# 411618_029_3_3.net
KiCad netlist of a schematic drawn in Altium Designer
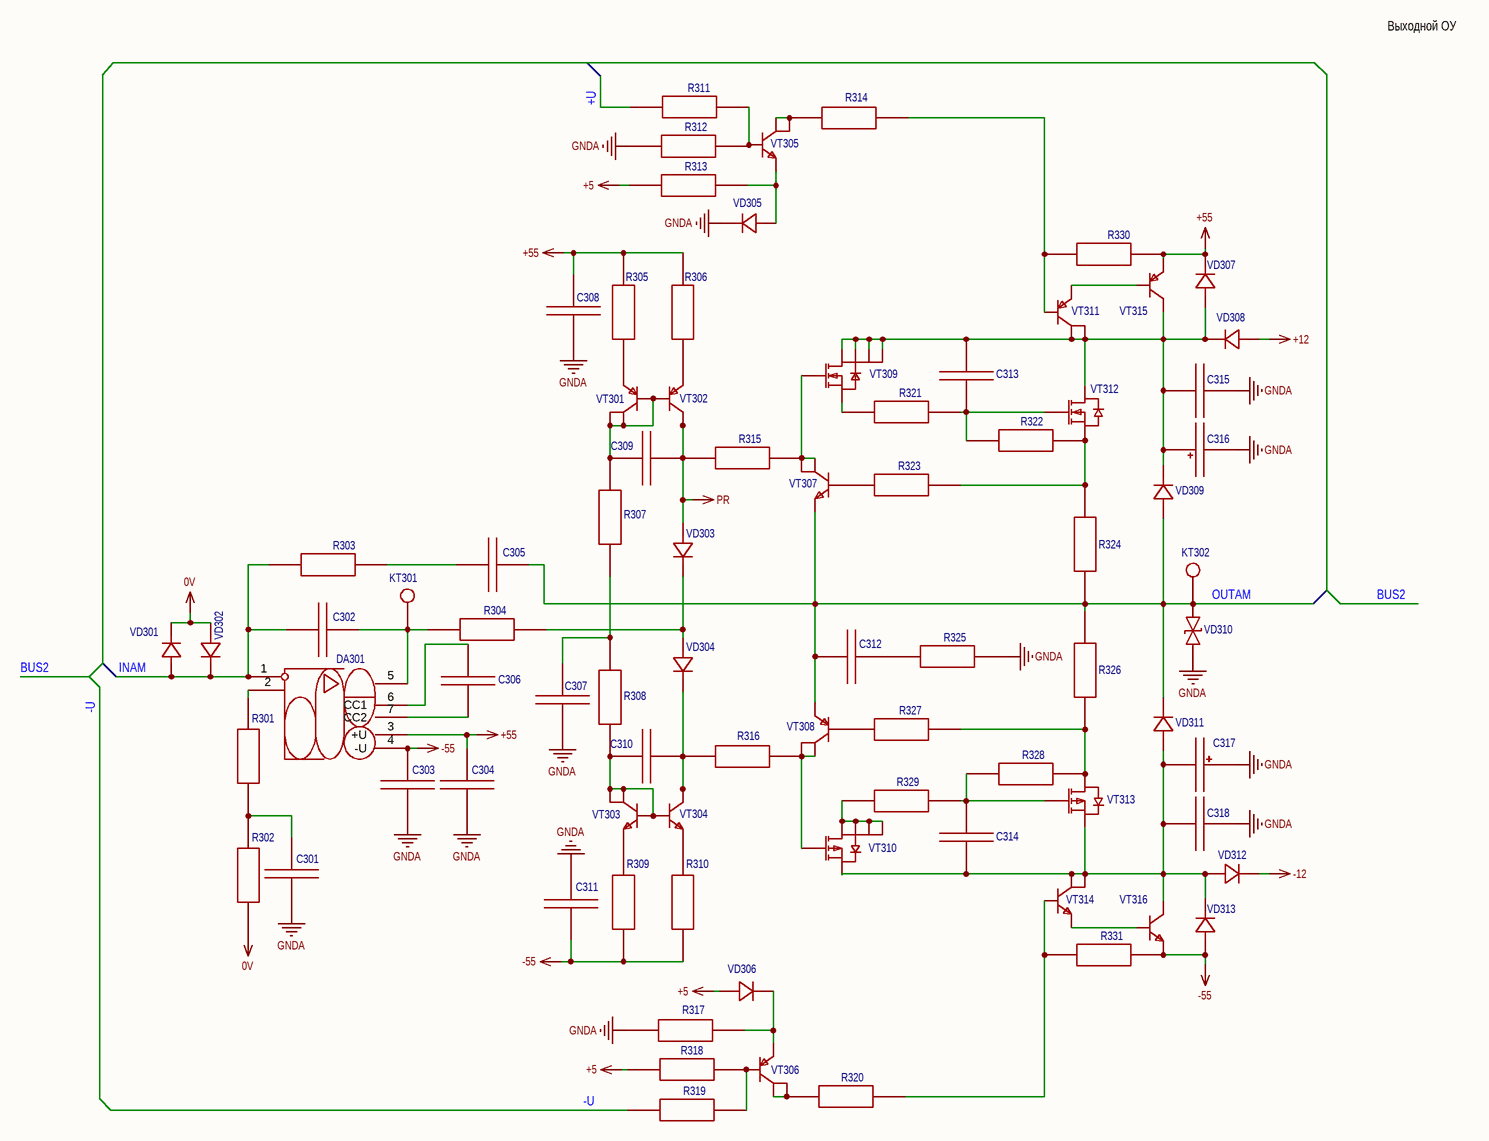
[diagram p0: УШЯИ.411618.029Э Э3 Лист 3.schdoc]

(export (version "E")
  (design (tool "Eeschema 10.0.6"))
  (components
    (comp (ref "C301")
      (value "Конденсатор SMD 1мкФ 100В X7R 10% [0805]")
      (footprint "C0805")
      (fields (field (name "MANUFACTURER PART") "C0805") (field (name "CONTRIBUTOR") "jordanjin"))
      (libsource (lib "altium-import") (part "root_1_Конденсатор SMD 1мкФ 100В X7R 10% [0805]_"))
    )
    (comp (ref "C302")
      (value "Конденсатор SMD 33пФ 100В X7R 10% [0805]")
      (footprint "C0805")
      (fields (field (name "MANUFACTURER PART") "C0805") (field (name "CONTRIBUTOR") "jordanjin"))
      (libsource (lib "altium-import") (part "root_2_Конденсатор SMD 33пФ 100В X7R 10% [0805]_"))
    )
    (comp (ref "C303")
      (value "Конденсатор SMD 68нФ 100В X7R 10% [0805]")
      (footprint "C0805")
      (fields (field (name "MANUFACTURER PART") "C0805") (field (name "CONTRIBUTOR") "jordanjin"))
      (libsource (lib "altium-import") (part "root_1_Конденсатор SMD 68нФ 100В X7R 10% [0805]_"))
    )
    (comp (ref "C304")
      (value "Конденсатор SMD 68нФ 100В X7R 10% [0805]")
      (footprint "C0805")
      (fields (field (name "MANUFACTURER PART") "C0805") (field (name "CONTRIBUTOR") "jordanjin"))
      (libsource (lib "altium-import") (part "root_1_Конденсатор SMD 68нФ 100В X7R 10% [0805]_"))
    )
    (comp (ref "C305")
      (value "Конденсатор SMD 10пФ 100В X7R 10% [0805]")
      (footprint "C0805")
      (fields (field (name "MANUFACTURER PART") "C0805") (field (name "CONTRIBUTOR") "jordanjin"))
      (libsource (lib "altium-import") (part "root_2_Конденсатор SMD 10пФ 100В X7R 10% [0805]_"))
    )
    (comp (ref "C306")
      (value "Конденсатор SMD 10пФ 100В X7R 10% [0805]")
      (footprint "C0805")
      (fields (field (name "MANUFACTURER PART") "C0805") (field (name "CONTRIBUTOR") "jordanjin"))
      (libsource (lib "altium-import") (part "root_3_Конденсатор SMD 10пФ 100В X7R 10% [0805]_"))
    )
    (comp (ref "C307")
      (value "Конденсатор SMD 68нФ 250В X7R 10% [0805]")
      (footprint "C0805")
      (fields (field (name "MANUFACTURER PART") "C0805") (field (name "CONTRIBUTOR") "jordanjin"))
      (libsource (lib "altium-import") (part "root_1_Конденсатор SMD 68нФ 250В X7R 10% [0805]_"))
    )
    (comp (ref "C308")
      (value "Конденсатор SMD 68нФ 250В X7R 10% [0805]")
      (footprint "C0805")
      (fields (field (name "MANUFACTURER PART") "C0805") (field (name "CONTRIBUTOR") "jordanjin"))
      (libsource (lib "altium-import") (part "root_3_Конденсатор SMD 68нФ 250В X7R 10% [0805]_"))
    )
    (comp (ref "C309")
      (value "Конденсатор SMD 10пФ 100В X7R 10% [0805]")
      (footprint "C0805")
      (fields (field (name "MANUFACTURER PART") "C0805") (field (name "CONTRIBUTOR") "jordanjin"))
      (libsource (lib "altium-import") (part "root_2_Конденсатор SMD 10пФ 100В X7R 10% [0805]_"))
    )
    (comp (ref "C310")
      (value "Конденсатор SMD 10пФ 100В X7R 10% [0805]")
      (footprint "C0805")
      (fields (field (name "MANUFACTURER PART") "C0805") (field (name "CONTRIBUTOR") "jordanjin"))
      (libsource (lib "") (part "root_2_Конденсатор SMD 10пФ 100В X7R 10% [0805]__1"))
    )
    (comp (ref "C311")
      (value "Конденсатор SMD 68нФ 250В X7R 10% [0805]")
      (footprint "C0805")
      (fields (field (name "MANUFACTURER PART") "C0805") (field (name "CONTRIBUTOR") "jordanjin"))
      (libsource (lib "altium-import") (part "root_3_Конденсатор SMD 68нФ 250В X7R 10% [0805]_"))
    )
    (comp (ref "C312")
      (value "Конденсатор SMD 10пФ 100В X7R 10% [0805]")
      (footprint "C0805")
      (fields (field (name "MANUFACTURER PART") "C0805") (field (name "CONTRIBUTOR") "jordanjin"))
      (libsource (lib "altium-import") (part "root_0_Конденсатор SMD 10пФ 100В X7R 10% [0805]_"))
    )
    (comp (ref "C313")
      (value "Конденсатор SMD 10пФ 100В X7R 10% [0805]")
      (footprint "C0805")
      (fields (field (name "MANUFACTURER PART") "C0805") (field (name "CONTRIBUTOR") "jordanjin"))
      (libsource (lib "altium-import") (part "root_3_Конденсатор SMD 10пФ 100В X7R 10% [0805]_"))
    )
    (comp (ref "C314")
      (value "Конденсатор SMD 10пФ 100В X7R 10% [0805]")
      (footprint "C0805")
      (fields (field (name "MANUFACTURER PART") "C0805") (field (name "CONTRIBUTOR") "jordanjin"))
      (libsource (lib "altium-import") (part "root_3_Конденсатор SMD 10пФ 100В X7R 10% [0805]_"))
    )
    (comp (ref "C315")
      (value "Конденсатор SMD 10пФ 100В X7R 10% [0805]")
      (footprint "C0805")
      (fields (field (name "MANUFACTURER PART") "C0805") (field (name "CONTRIBUTOR") "jordanjin"))
      (libsource (lib "altium-import") (part "root_0_Конденсатор SMD 10пФ 100В X7R 10% [0805]_"))
    )
    (comp (ref "C316")
      (value "ECAP (К50-35), 220мкФ, 100В, 105°C, 13x25, p:5мм")
      (footprint "CAP-TH_BD13.0-P5.00-D0.6-FD")
      (fields
        (field (name "MANUFACTURER") "JB Capacitors")
        (field (name "MANUFACTURER PART") "JRB2A221M05001300250000B")
        (field (name "CONTRIBUTOR") "jordanjin")
      )
      (libsource (lib "altium-import") (part "root_1_ECAP (К50-35), 220мкФ, 100В, 105°C, 13x25, p{colon}5мм_"))
    )
    (comp (ref "C317")
      (value "ECAP (К50-35), 220мкФ, 100В, 105°C, 13x25, p:5мм")
      (footprint "CAP-TH_BD13.0-P5.00-D0.6-FD")
      (fields
        (field (name "MANUFACTURER") "JB Capacitors")
        (field (name "MANUFACTURER PART") "JRB2A221M05001300250000B")
        (field (name "CONTRIBUTOR") "jordanjin")
      )
      (libsource (lib "altium-import") (part "root_3_ECAP (К50-35), 220мкФ, 100В, 105°C, 13x25, p{colon}5мм_"))
    )
    (comp (ref "C318")
      (value "Конденсатор SMD 10пФ 100В X7R 10% [0805]")
      (footprint "C0805")
      (fields (field (name "MANUFACTURER PART") "C0805") (field (name "CONTRIBUTOR") "jordanjin"))
      (libsource (lib "altium-import") (part "root_0_Конденсатор SMD 10пФ 100В X7R 10% [0805]_"))
    )
    (comp (ref "DA301")
      (value "Операционный усилитель PA340CC [TH]")
      (fields
        (field (name "MANUFACTURER") "Apex Microtechnology")
        (field (name "MANUFACTURER PART") "PA340CC")
        (field (name "CONTRIBUTOR") "jordanjin")
      )
      (libsource (lib "altium-import") (part "root_0_Операционный усилитель PA340CC [TH]_"))
    )
    (comp (ref "KT301")
      (value "Control point")
      (fields (field (name "CONTRIBUTOR") "jordanjin"))
      (libsource (lib "altium-import") (part "root_2_Control point_"))
    )
    (comp (ref "KT302")
      (value "Control point")
      (fields (field (name "CONTRIBUTOR") "jordanjin"))
      (libsource (lib "altium-import") (part "root_2_Control point_"))
    )
    (comp (ref "R301")
      (value "Резистор 4.6кОм 0,125Вт 1% [0805]")
      (footprint "R0805")
      (fields (field (name "MANUFACTURER PART") "R0805") (field (name "CONTRIBUTOR") "jordanjin"))
      (libsource (lib "altium-import") (part "root_1_Резистор 4.6кОм 0,125Вт 1% [0805]_"))
    )
    (comp (ref "R302")
      (value "Резистор 1.2кОм 0,125Вт 1% [0805]")
      (footprint "R0805")
      (fields (field (name "MANUFACTURER PART") "R0805") (field (name "CONTRIBUTOR") "jordanjin"))
      (libsource (lib "altium-import") (part "root_1_Резистор 1.2кОм 0,125Вт 1% [0805]_"))
    )
    (comp (ref "R303")
      (value "Резистор 1.8кОм 0,125Вт 1% [0805]")
      (footprint "R0805")
      (fields (field (name "MANUFACTURER PART") "R0805") (field (name "CONTRIBUTOR") "jordanjin"))
      (libsource (lib "altium-import") (part "root_2_Резистор 1.8кОм 0,125Вт 1% [0805]_"))
    )
    (comp (ref "R304")
      (value "Резистор 1.2кОм 0,125Вт 1% [0805]")
      (footprint "R0805")
      (fields (field (name "MANUFACTURER PART") "R0805") (field (name "CONTRIBUTOR") "jordanjin"))
      (libsource (lib "altium-import") (part "root_2_Резистор 1.2кОм 0,125Вт 1% [0805]_"))
    )
    (comp (ref "R305")
      (value "Резистор 220Ом 0,125Вт 1% [0805]")
      (footprint "R0805")
      (fields (field (name "MANUFACTURER PART") "R0805") (field (name "CONTRIBUTOR") "jordanjin"))
      (libsource (lib "") (part "root_3_Резистор 220Ом 0,125Вт 1% [0805]__1"))
    )
    (comp (ref "R306")
      (value "Резистор 220Ом 0,125Вт 1% [0805]")
      (footprint "R0805")
      (fields (field (name "MANUFACTURER PART") "R0805") (field (name "CONTRIBUTOR") "jordanjin"))
      (libsource (lib "") (part "root_3_Резистор 220Ом 0,125Вт 1% [0805]__1"))
    )
    (comp (ref "R307")
      (value "Резистор 22кОм 0,125Вт 1% [0805]")
      (footprint "R0805")
      (fields (field (name "MANUFACTURER PART") "R0805") (field (name "CONTRIBUTOR") "jordanjin"))
      (libsource (lib "") (part "root_3_Резистор 22кОм 0,125Вт 1% [0805]__1"))
    )
    (comp (ref "R308")
      (value "Резистор 22кОм 0,125Вт 1% [0805]")
      (footprint "R0805")
      (fields (field (name "MANUFACTURER PART") "R0805") (field (name "CONTRIBUTOR") "jordanjin"))
      (libsource (lib "altium-import") (part "root_3_Резистор 22кОм 0,125Вт 1% [0805]_"))
    )
    (comp (ref "R309")
      (value "Резистор 220Ом 0,125Вт 1% [0805]")
      (footprint "R0805")
      (fields (field (name "MANUFACTURER PART") "R0805") (field (name "CONTRIBUTOR") "jordanjin"))
      (libsource (lib "altium-import") (part "root_3_Резистор 220Ом 0,125Вт 1% [0805]_"))
    )
    (comp (ref "R310")
      (value "Резистор 220Ом 0,125Вт 1% [0805]")
      (footprint "R0805")
      (fields (field (name "MANUFACTURER PART") "R0805") (field (name "CONTRIBUTOR") "jordanjin"))
      (libsource (lib "altium-import") (part "root_3_Резистор 220Ом 0,125Вт 1% [0805]_"))
    )
    (comp (ref "R311")
      (value "Резистор 3кОм 0,125Вт 1% [0805]")
      (footprint "R0805")
      (fields (field (name "MANUFACTURER PART") "R0805") (field (name "CONTRIBUTOR") "jordanjin"))
      (libsource (lib "") (part "root_0_Резистор 3кОм 0,125Вт 1% [0805]__1"))
    )
    (comp (ref "R312")
      (value "Резистор 2.4кОм 0,125Вт 1% [0805]")
      (footprint "R0805")
      (fields (field (name "MANUFACTURER PART") "R0805") (field (name "CONTRIBUTOR") "jordanjin"))
      (libsource (lib "altium-import") (part "root_0_Резистор 2.4кОм 0,125Вт 1% [0805]_"))
    )
    (comp (ref "R313")
      (value "Резистор 7.2кОм 0,125Вт 1% [0805]")
      (footprint "R0805")
      (fields (field (name "MANUFACTURER PART") "R0805") (field (name "CONTRIBUTOR") "jordanjin"))
      (libsource (lib "") (part "root_0_Резистор 7.2кОм 0,125Вт 1% [0805]__1"))
    )
    (comp (ref "R314")
      (value "Резистор 18кОм 0,125Вт 1% [0805]")
      (footprint "R0805")
      (fields (field (name "MANUFACTURER PART") "R0805") (field (name "CONTRIBUTOR") "jordanjin"))
      (libsource (lib "") (part "root_0_Резистор 18кОм 0,125Вт 1% [0805]__1"))
    )
    (comp (ref "R315")
      (value "Резистор 120Ом 0,125Вт 1% [0805]")
      (footprint "R0805")
      (fields (field (name "MANUFACTURER PART") "R0805") (field (name "CONTRIBUTOR") "jordanjin"))
      (libsource (lib "altium-import") (part "root_0_Резистор 120Ом 0,125Вт 1% [0805]_"))
    )
    (comp (ref "R316")
      (value "Резистор 120Ом 0,125Вт 1% [0805]")
      (footprint "R0805")
      (fields (field (name "MANUFACTURER PART") "R0805") (field (name "CONTRIBUTOR") "jordanjin"))
      (libsource (lib "altium-import") (part "root_0_Резистор 120Ом 0,125Вт 1% [0805]_"))
    )
    (comp (ref "R317")
      (value "Резистор 7.2кОм 0,125Вт 1% [0805]")
      (footprint "R0805")
      (fields (field (name "MANUFACTURER PART") "R0805") (field (name "CONTRIBUTOR") "jordanjin"))
      (libsource (lib "altium-import") (part "root_0_Резистор 7.2кОм 0,125Вт 1% [0805]_"))
    )
    (comp (ref "R318")
      (value "Резистор 2.4кОм 0,125Вт 1% [0805]")
      (footprint "R0805")
      (fields (field (name "MANUFACTURER PART") "R0805") (field (name "CONTRIBUTOR") "jordanjin"))
      (libsource (lib "") (part "root_0_Резистор 2.4кОм 0,125Вт 1% [0805]__1"))
    )
    (comp (ref "R319")
      (value "Резистор 3кОм 0,125Вт 1% [0805]")
      (footprint "R0805")
      (fields (field (name "MANUFACTURER PART") "R0805") (field (name "CONTRIBUTOR") "jordanjin"))
      (libsource (lib "altium-import") (part "root_0_Резистор 3кОм 0,125Вт 1% [0805]_"))
    )
    (comp (ref "R320")
      (value "Резистор 18кОм 0,125Вт 1% [0805]")
      (footprint "R0805")
      (fields (field (name "MANUFACTURER PART") "R0805") (field (name "CONTRIBUTOR") "jordanjin"))
      (libsource (lib "altium-import") (part "root_0_Резистор 18кОм 0,125Вт 1% [0805]_"))
    )
    (comp (ref "R321")
      (value "Резистор 240Ом 0.25Вт 1% [1206]")
      (footprint "R0805")
      (fields (field (name "MANUFACTURER PART") "R0805") (field (name "CONTRIBUTOR") "jordanjin"))
      (libsource (lib "altium-import") (part "root_0_Резистор 240Ом 0.25Вт 1% [1206]_"))
    )
    (comp (ref "R322")
      (value "Резистор 1кОм 0,125Вт 5% [0805]")
      (footprint "R0805")
      (fields (field (name "MANUFACTURER PART") "R0805") (field (name "CONTRIBUTOR") "jordanjin"))
      (libsource (lib "altium-import") (part "root_2_Резистор 1кОм 0,125Вт 5% [0805]_"))
    )
    (comp (ref "R323")
      (value "Резистор 300Ом 0,125Вт 1% [0805]")
      (footprint "R0805")
      (fields (field (name "MANUFACTURER PART") "R0805") (field (name "CONTRIBUTOR") "jordanjin"))
      (libsource (lib "altium-import") (part "root_0_Резистор 300Ом 0,125Вт 1% [0805]_"))
    )
    (comp (ref "R324")
      (value "Резистор MP930-0.04-1% [TO-220-2]")
      (footprint "TO-220-2_L10.4-W3.2-P5.08-L")
      (fields (field (name "MANUFACTURER PART") "MP930-0.04-1%") (field (name "CONTRIBUTOR") "jordanjin"))
      (libsource (lib "altium-import") (part "root_1_Резистор MP930-0.04-1% [TO-220-2]_"))
    )
    (comp (ref "R325")
      (value "Резистор 100Ом 0,125Вт 1% [0805]")
      (footprint "R0805")
      (fields (field (name "MANUFACTURER PART") "R0805") (field (name "CONTRIBUTOR") "jordanjin"))
      (libsource (lib "altium-import") (part "root_0_Резистор 100Ом 0,125Вт 1% [0805]_"))
    )
    (comp (ref "R326")
      (value "Резистор MP930-0.04-1% [TO-220-2]")
      (footprint "TO-220-2_L10.4-W3.2-P5.08-L")
      (fields (field (name "MANUFACTURER PART") "MP930-0.04-1%") (field (name "CONTRIBUTOR") "jordanjin"))
      (libsource (lib "") (part "root_1_Резистор MP930-0.04-1% [TO-220-2]__1"))
    )
    (comp (ref "R327")
      (value "Резистор 300Ом 0,125Вт 1% [0805]")
      (footprint "R0805")
      (fields (field (name "MANUFACTURER PART") "R0805") (field (name "CONTRIBUTOR") "jordanjin"))
      (libsource (lib "") (part "root_0_Резистор 300Ом 0,125Вт 1% [0805]__1"))
    )
    (comp (ref "R328")
      (value "Резистор 1кОм 0,125Вт 5% [0805]")
      (footprint "R0805")
      (fields (field (name "MANUFACTURER PART") "R0805") (field (name "CONTRIBUTOR") "jordanjin"))
      (libsource (lib "altium-import") (part "root_0_Резистор 1кОм 0,125Вт 5% [0805]_"))
    )
    (comp (ref "R329")
      (value "Резистор 240Ом 0.25Вт 1% [1206]")
      (footprint "R0805")
      (fields (field (name "MANUFACTURER PART") "R0805") (field (name "CONTRIBUTOR") "jordanjin"))
      (libsource (lib "") (part "root_0_Резистор 240Ом 0.25Вт 1% [1206]__1"))
    )
    (comp (ref "R330")
      (value "Резистор 1.5кОм 0,125Вт 1% [0805]")
      (footprint "R0805")
      (fields (field (name "MANUFACTURER PART") "R0805") (field (name "CONTRIBUTOR") "jordanjin"))
      (libsource (lib "altium-import") (part "root_0_Резистор 1.5кОм 0,125Вт 1% [0805]_"))
    )
    (comp (ref "R331")
      (value "Резистор 1.5кОм 0,125Вт 1% [0805]")
      (footprint "R0805")
      (fields (field (name "MANUFACTURER PART") "R0805") (field (name "CONTRIBUTOR") "jordanjin"))
      (libsource (lib "altium-import") (part "root_0_Резистор 1.5кОм 0,125Вт 1% [0805]_"))
    )
    (comp (ref "VD301")
      (value "Диод импульсный 1N4448 [SOD-123]")
      (footprint "SOD-123_L2.7-W1.6-LS3.7-RD-1")
      (fields
        (field (name "MANUFACTURER") "YANGJIE")
        (field (name "MANUFACTURER PART") "1N4448WQ")
        (field (name "CONTRIBUTOR") "jordanjin")
      )
      (libsource (lib "") (part "root_3_Диод импульсный 1N4448 [SOD-123]__1"))
    )
    (comp (ref "VD302")
      (value "Диод импульсный 1N4448 [SOD-123]")
      (footprint "SOD-123_L2.7-W1.6-LS3.7-RD-1")
      (fields
        (field (name "MANUFACTURER") "YANGJIE")
        (field (name "MANUFACTURER PART") "1N4448WQ")
        (field (name "CONTRIBUTOR") "jordanjin")
      )
      (libsource (lib "altium-import") (part "root_1_Диод импульсный 1N4448 [SOD-123]_"))
    )
    (comp (ref "VD303")
      (value "Диод импульсный 1N4448 [SOD-123]")
      (footprint "SOD-123_L2.7-W1.6-LS3.7-RD-1")
      (fields
        (field (name "MANUFACTURER") "YANGJIE")
        (field (name "MANUFACTURER PART") "1N4448WQ")
        (field (name "CONTRIBUTOR") "jordanjin")
      )
      (libsource (lib "altium-import") (part "root_1_Диод импульсный 1N4448 [SOD-123]_"))
    )
    (comp (ref "VD304")
      (value "Диод импульсный 1N4448 [SOD-123]")
      (footprint "SOD-123_L2.7-W1.6-LS3.7-RD-1")
      (fields
        (field (name "MANUFACTURER") "YANGJIE")
        (field (name "MANUFACTURER PART") "1N4448WQ")
        (field (name "CONTRIBUTOR") "jordanjin")
      )
      (libsource (lib "altium-import") (part "root_3_Диод импульсный 1N4448 [SOD-123]_"))
    )
    (comp (ref "VD305")
      (value "Диод импульсный 1N4448 [SOD-123]")
      (footprint "SOD-123_L2.7-W1.6-LS3.7-RD-1")
      (fields
        (field (name "MANUFACTURER") "YANGJIE")
        (field (name "MANUFACTURER PART") "1N4448WQ")
        (field (name "CONTRIBUTOR") "jordanjin")
      )
      (libsource (lib "altium-import") (part "root_0_Диод импульсный 1N4448 [SOD-123]_"))
    )
    (comp (ref "VD306")
      (value "Диод импульсный 1N4448 [SOD-123]")
      (footprint "SOD-123_L2.7-W1.6-LS3.7-RD-1")
      (fields
        (field (name "MANUFACTURER") "YANGJIE")
        (field (name "MANUFACTURER PART") "1N4448WQ")
        (field (name "CONTRIBUTOR") "jordanjin")
      )
      (libsource (lib "altium-import") (part "root_2_Диод импульсный 1N4448 [SOD-123]_"))
    )
    (comp (ref "VD307")
      (value "Диод RS1M [SMA] (допускается замена на FR307 [DO-201AD])")
      (fields
        (field (name "MANUFACTURER") "Wild Goose(威谷)")
        (field (name "MANUFACTURER PART") "RS1M")
        (field (name "CONTRIBUTOR") "lcsc")
      )
      (libsource (lib "altium-import") (part "root_3_Диод RS1M [SMA] (допускается замена на FR307 [DO-201AD])_"))
    )
    (comp (ref "VD308")
      (value "Диод КД2970А [TO-220AC]")
      (footprint "TO-220AC-2_L10.0-W4.5-P5.08-T")
      (fields
        (field (name "MANUFACTURER") "NH(纽航)")
        (field (name "MANUFACTURER PART") "MUR1560F")
        (field (name "CONTRIBUTOR") "lcsc")
      )
      (libsource (lib "altium-import") (part "root_0_Диод КД2970А [TO-220AC]_"))
    )
    (comp (ref "VD309")
      (value "Диод RS1M [SMA] (допускается замена на FR307 [DO-201AD])")
      (fields
        (field (name "MANUFACTURER") "Wild Goose(威谷)")
        (field (name "MANUFACTURER PART") "RS1M")
        (field (name "CONTRIBUTOR") "lcsc")
      )
      (libsource (lib "altium-import") (part "root_3_Диод RS1M [SMA] (допускается замена на FR307 [DO-201AD])_"))
    )
    (comp (ref "VD310")
      (value "Диод защитный 1.5KE56CA [DO-201AD/DO-27]")
      (footprint "DO-201")
      (fields
        (field (name "MANUFACTURER") "Littelfuse(美国力特)")
        (field (name "MANUFACTURER PART") "1.5KE56CA")
        (field (name "CONTRIBUTOR") "LCSC")
      )
      (libsource (lib "altium-import") (part "root_1_Диод защитный 1.5KE56CA [DO-201AD/DO-27]_"))
    )
    (comp (ref "VD311")
      (value "Диод RS1M [SMA] (допускается замена на FR307 [DO-201AD])")
      (fields
        (field (name "MANUFACTURER") "Wild Goose(威谷)")
        (field (name "MANUFACTURER PART") "RS1M")
        (field (name "CONTRIBUTOR") "lcsc")
      )
      (libsource (lib "altium-import") (part "root_3_Диод RS1M [SMA] (допускается замена на FR307 [DO-201AD])_"))
    )
    (comp (ref "VD312")
      (value "Диод КД2970А [TO-220AC]")
      (footprint "TO-220AC-2_L10.0-W4.5-P5.08-T")
      (fields
        (field (name "MANUFACTURER") "NH(纽航)")
        (field (name "MANUFACTURER PART") "MUR1560F")
        (field (name "CONTRIBUTOR") "lcsc")
      )
      (libsource (lib "altium-import") (part "root_2_Диод КД2970А [TO-220AC]_"))
    )
    (comp (ref "VD313")
      (value "Диод RS1M [SMA] (допускается замена на FR307 [DO-201AD])")
      (fields
        (field (name "MANUFACTURER") "Wild Goose(威谷)")
        (field (name "MANUFACTURER PART") "RS1M")
        (field (name "CONTRIBUTOR") "lcsc")
      )
      (libsource (lib "altium-import") (part "root_3_Диод RS1M [SMA] (допускается замена на FR307 [DO-201AD])_"))
    )
    (comp (ref "VT301")
      (value "Транзистор DZTA92 PNP [SOT223]")
      (footprint "SOT-223-3_L6.5-W3.4-P2.30-LS7.0-BR")
      (fields
        (field (name "MANUFACTURER") "DIODES(美台)")
        (field (name "MANUFACTURER PART") "DZTA92-13")
        (field (name "CONTRIBUTOR") "lcsc")
      )
      (libsource (lib "") (part "root_0_Транзистор DZTA92 PNP [SOT223]__1"))
    )
    (comp (ref "VT302")
      (value "Транзистор FZT758 PNP [SOT223]")
      (footprint "SOT-223_L6.5-W3.5-P2.30-LS7.0-BR")
      (fields
        (field (name "MANUFACTURER") "DIODES(美台)")
        (field (name "MANUFACTURER PART") "FZT758TA")
        (field (name "CONTRIBUTOR") "LCSC")
      )
      (libsource (lib "altium-import") (part "root_0_Транзистор FZT758 PNP [SOT223]_"))
    )
    (comp (ref "VT303")
      (value "Транзистор DZTA42 NPN [SOT223]")
      (footprint "SOT-223-4_L6.5-W3.5-P2.30-LS7.0-BR")
      (fields
        (field (name "MANUFACTURER") "DIODES(美台)")
        (field (name "MANUFACTURER PART") "DZTA42-13")
        (field (name "CONTRIBUTOR") "LCSC")
      )
      (libsource (lib "") (part "root_0_Транзистор DZTA42 NPN [SOT223]__1"))
    )
    (comp (ref "VT304")
      (value "Транзистор FZT658 NPN [SOT223]")
      (footprint "SOT-223_L6.5-W3.5-P2.30-LS7.0-BR")
      (fields
        (field (name "MANUFACTURER") "DIODES(美台)")
        (field (name "MANUFACTURER PART") "FZT658")
        (field (name "CONTRIBUTOR") "lcsc")
      )
      (libsource (lib "altium-import") (part "root_0_Транзистор FZT658 NPN [SOT223]_"))
    )
    (comp (ref "VT305")
      (value "Транзистор DZTA42 NPN [SOT223]")
      (footprint "SOT-223-4_L6.5-W3.5-P2.30-LS7.0-BR")
      (fields
        (field (name "MANUFACTURER") "DIODES(美台)")
        (field (name "MANUFACTURER PART") "DZTA42-13")
        (field (name "CONTRIBUTOR") "LCSC")
      )
      (libsource (lib "altium-import") (part "root_0_Транзистор DZTA42 NPN [SOT223]_"))
    )
    (comp (ref "VT306")
      (value "Транзистор DZTA92 PNP [SOT223]")
      (footprint "SOT-223-3_L6.5-W3.4-P2.30-LS7.0-BR")
      (fields
        (field (name "MANUFACTURER") "DIODES(美台)")
        (field (name "MANUFACTURER PART") "DZTA92-13")
        (field (name "CONTRIBUTOR") "lcsc")
      )
      (libsource (lib "altium-import") (part "root_0_Транзистор DZTA92 PNP [SOT223]_"))
    )
    (comp (ref "VT307")
      (value "Транзистор DZTA42 NPN [SOT223]")
      (footprint "SOT-223-4_L6.5-W3.5-P2.30-LS7.0-BR")
      (fields
        (field (name "MANUFACTURER") "DIODES(美台)")
        (field (name "MANUFACTURER PART") "DZTA42-13")
        (field (name "CONTRIBUTOR") "LCSC")
      )
      (libsource (lib "") (part "root_0_Транзистор DZTA42 NPN [SOT223]__1"))
    )
    (comp (ref "VT308")
      (value "Транзистор DZTA92 PNP [SOT223]")
      (footprint "SOT-223-3_L6.5-W3.4-P2.30-LS7.0-BR")
      (fields
        (field (name "MANUFACTURER") "DIODES(美台)")
        (field (name "MANUFACTURER PART") "DZTA92-13")
        (field (name "CONTRIBUTOR") "lcsc")
      )
      (libsource (lib "") (part "root_0_Транзистор DZTA92 PNP [SOT223]__1"))
    )
    (comp (ref "VT309")
      (value "Транзистор ZXMN10A08E6 N-канал 100В 1.9А [SOT-23-6]")
      (footprint "SOT-23-6_L2.9-W1.6-P0.95-LS2.7-BL")
      (fields
        (field (name "MANUFACTURER") "VBsemi(微碧半导体)")
        (field (name "MANUFACTURER PART") "ZXMN10A08E6TA-VB")
        (field (name "CONTRIBUTOR") "lcsc")
      )
      (libsource (lib "altium-import") (part "root_0_Транзистор ZXMN10A08E6 N-канал 100В 1.9А [SOT-23-6]_"))
    )
    (comp (ref "VT310")
      (value "Транзистор ZXMP10A17E6 P-канал 100В 1.3А [SOT-23-6]")
      (footprint "SOT-23-6_L2.9-W1.6-P0.95-LS2.8-BL")
      (fields
        (field (name "MANUFACTURER") "DIODES(美台)")
        (field (name "MANUFACTURER PART") "ZXMP10A17E6QTA")
        (field (name "CONTRIBUTOR") "lcsc")
      )
      (libsource (lib "altium-import") (part "root_0_Транзистор ZXMP10A17E6 P-канал 100В 1.3А [SOT-23-6]_"))
    )
    (comp (ref "VT311")
      (value "Транзистор DZTA92 PNP [SOT223]")
      (footprint "SOT-223-3_L6.5-W3.4-P2.30-LS7.0-BR")
      (fields
        (field (name "MANUFACTURER") "DIODES(美台)")
        (field (name "MANUFACTURER PART") "DZTA92-13")
        (field (name "CONTRIBUTOR") "lcsc")
      )
      (libsource (lib "altium-import") (part "root_0_Транзистор DZTA92 PNP [SOT223]_"))
    )
    (comp (ref "VT312")
      (value "Транзистор FQP13N10  N-канал 100В 12.8А [TO-220]")
      (fields
        (field (name "MANUFACTURER") "onsemi(安森美)")
        (field (name "MANUFACTURER PART") "FQP13N10")
        (field (name "CONTRIBUTOR") "lcsc")
      )
      (libsource (lib "altium-import") (part "root_0_Транзистор FQP13N10  N-канал 100В 12.8А [TO-220]_"))
    )
    (comp (ref "VT313")
      (value "Транзистор SFP9530 P-канал 100В 10.5А [TO-220]")
      (fields
        (field (name "MANUFACTURER") "onsemi")
        (field (name "MANUFACTURER PART") "SFP9530")
        (field (name "CONTRIBUTOR") "jordanjin")
      )
      (libsource (lib "altium-import") (part "root_0_Транзистор SFP9530 P-канал 100В 10.5А [TO-220]_"))
    )
    (comp (ref "VT314")
      (value "Транзистор DZTA42 NPN [SOT223]")
      (footprint "SOT-223-4_L6.5-W3.5-P2.30-LS7.0-BR")
      (fields
        (field (name "MANUFACTURER") "DIODES(美台)")
        (field (name "MANUFACTURER PART") "DZTA42-13")
        (field (name "CONTRIBUTOR") "LCSC")
      )
      (libsource (lib "altium-import") (part "root_0_Транзистор DZTA42 NPN [SOT223]_"))
    )
    (comp (ref "VT315")
      (value "Транзистор MJE5730G PNP [TO-220-3]")
      (footprint "TO-220-3_L10.0-W4.5-P2.54-L")
      (fields
        (field (name "MANUFACTURER") "onsemi(安森美)")
        (field (name "MANUFACTURER PART") "MJE5730G")
        (field (name "CONTRIBUTOR") "LCSC")
      )
      (libsource (lib "altium-import") (part "root_0_Транзистор MJE5730G PNP [TO-220-3]_"))
    )
    (comp (ref "VT316")
      (value "Транзистор TIP48 NPN [TO-220-3]")
      (footprint "TO-220-3_L10.0-W4.5-P2.54-L")
      (fields
        (field (name "MANUFACTURER") "onsemi(安森美)")
        (field (name "MANUFACTURER PART") "TIP48G")
        (field (name "CONTRIBUTOR") "lcsc")
      )
      (libsource (lib "altium-import") (part "root_0_Транзистор TIP48 NPN [TO-220-3]_"))
    )
  )
  (nets
    (net (code "2") (name "+5") (class "Default")
      (node (ref "R313") (pin "1") (pinfunction "1_1") (pintype "passive"))
      (node (ref "R318") (pin "1") (pinfunction "1_1") (pintype "passive"))
      (node (ref "VD306") (pin "2") (pinfunction "A_2") (pintype "passive"))
    )
    (net (code "3") (name "+12") (class "Default")
      (node (ref "VD308") (pin "3") (pinfunction "A_3") (pintype "passive"))
    )
    (net (code "4") (name "+55") (class "Default")
      (node (ref "C304") (pin "2") (pinfunction "2_2") (pintype "passive"))
      (node (ref "C308") (pin "1") (pinfunction "1_1") (pintype "passive"))
      (node (ref "DA301") (pin "3") (pinfunction "+U_3") (pintype "passive"))
      (node (ref "R305") (pin "1") (pinfunction "1_1") (pintype "passive"))
      (node (ref "R306") (pin "1") (pinfunction "1_1") (pintype "passive"))
      (node (ref "R330") (pin "2") (pinfunction "2_2") (pintype "passive"))
      (node (ref "VD307") (pin "1") (pinfunction "K_1") (pintype "passive"))
      (node (ref "VT315") (pin "3") (pinfunction "E_3") (pintype "passive"))
    )
    (net (code "5") (name "-12") (class "Default")
      (node (ref "VD312") (pin "1") (pinfunction "K_1") (pintype "passive"))
    )
    (net (code "6") (name "-55") (class "Default")
      (node (ref "C303") (pin "2") (pinfunction "2_2") (pintype "passive"))
      (node (ref "C311") (pin "2") (pinfunction "2_2") (pintype "passive"))
      (node (ref "DA301") (pin "4") (pinfunction "-U_4") (pintype "passive"))
      (node (ref "R309") (pin "1") (pinfunction "1_1") (pintype "passive"))
      (node (ref "R310") (pin "1") (pinfunction "1_1") (pintype "passive"))
      (node (ref "R331") (pin "2") (pinfunction "2_2") (pintype "passive"))
      (node (ref "VD313") (pin "2") (pinfunction "A_2") (pintype "passive"))
      (node (ref "VT316") (pin "3") (pinfunction "E_3") (pintype "passive"))
    )
    (net (code "7") (name "/+U") (class "Default")
      (node (ref "R311") (pin "1") (pinfunction "1_1") (pintype "passive"))
    )
    (net (code "8") (name "/-U") (class "Default")
      (node (ref "R319") (pin "1") (pinfunction "1_1") (pintype "passive"))
    )
    (net (code "9") (name "/INAM") (class "Default")
      (node (ref "C302") (pin "2") (pinfunction "2_2") (pintype "passive"))
      (node (ref "DA301") (pin "1") (pinfunction "-_1") (pintype "passive"))
      (node (ref "R303") (pin "2") (pinfunction "2_2") (pintype "passive"))
      (node (ref "VD301") (pin "2") (pinfunction "A_2") (pintype "passive"))
      (node (ref "VD302") (pin "1") (pinfunction "C_1") (pintype "passive"))
    )
    (net (code "10") (name "/OUTAM") (class "Default")
      (node (ref "C305") (pin "1") (pinfunction "1_1") (pintype "passive"))
      (node (ref "C312") (pin "1") (pinfunction "1_1") (pintype "passive"))
      (node (ref "KT302") (pin "1") (pinfunction "1_1") (pintype "passive"))
      (node (ref "R324") (pin "1") (pinfunction "1_1") (pintype "passive"))
      (node (ref "R326") (pin "2") (pinfunction "2_2") (pintype "passive"))
      (node (ref "VD309") (pin "2") (pinfunction "A_2") (pintype "passive"))
      (node (ref "VD310") (pin "2") (pinfunction "2_2") (pintype "passive"))
      (node (ref "VD311") (pin "1") (pinfunction "K_1") (pintype "passive"))
      (node (ref "VT307") (pin "3") (pinfunction "E_3") (pintype "passive"))
      (node (ref "VT308") (pin "3") (pinfunction "E_3") (pintype "passive"))
    )
    (net (code "12") (name "0V") (class "Default")
      (node (ref "R302") (pin "1") (pinfunction "1_1") (pintype "passive"))
      (node (ref "VD301") (pin "1") (pinfunction "C_1") (pintype "passive"))
      (node (ref "VD302") (pin "2") (pinfunction "A_2") (pintype "passive"))
    )
    (net (code "13") (name "GNDA") (class "Default")
      (node (ref "C301") (pin "1") (pinfunction "1_1") (pintype "passive"))
      (node (ref "C303") (pin "1") (pinfunction "1_1") (pintype "passive"))
      (node (ref "C304") (pin "1") (pinfunction "1_1") (pintype "passive"))
      (node (ref "C307") (pin "1") (pinfunction "1_1") (pintype "passive"))
      (node (ref "C308") (pin "2") (pinfunction "2_2") (pintype "passive"))
      (node (ref "C311") (pin "1") (pinfunction "1_1") (pintype "passive"))
      (node (ref "C315") (pin "2") (pinfunction "2_2") (pintype "passive"))
      (node (ref "C316") (pin "2") (pinfunction "2_2") (pintype "passive"))
      (node (ref "C317") (pin "1") (pinfunction "1_1") (pintype "passive"))
      (node (ref "C318") (pin "2") (pinfunction "2_2") (pintype "passive"))
      (node (ref "R312") (pin "1") (pinfunction "1_1") (pintype "passive"))
      (node (ref "R317") (pin "1") (pinfunction "1_1") (pintype "passive"))
      (node (ref "R325") (pin "2") (pinfunction "2_2") (pintype "passive"))
      (node (ref "VD305") (pin "1") (pinfunction "C_1") (pintype "passive"))
      (node (ref "VD310") (pin "1") (pinfunction "1_1") (pintype "passive"))
    )
    (net (code "14") (name "Net-(C301-Pad2)") (class "Default")
      (node (ref "C301") (pin "2") (pinfunction "2_2") (pintype "passive"))
      (node (ref "R301") (pin "1") (pinfunction "1_1") (pintype "passive"))
      (node (ref "R302") (pin "2") (pinfunction "2_2") (pintype "passive"))
    )
    (net (code "15") (name "Net-(C305-Pad2)") (class "Default")
      (node (ref "C305") (pin "2") (pinfunction "2_2") (pintype "passive"))
      (node (ref "R303") (pin "1") (pinfunction "1_1") (pintype "passive"))
    )
    (net (code "16") (name "Net-(C307-Pad2)") (class "Default")
      (node (ref "C307") (pin "2") (pinfunction "2_2") (pintype "passive"))
      (node (ref "R307") (pin "2") (pinfunction "2_2") (pintype "passive"))
      (node (ref "R308") (pin "2") (pinfunction "2_2") (pintype "passive"))
    )
    (net (code "17") (name "Net-(C312-Pad2)") (class "Default")
      (node (ref "C312") (pin "2") (pinfunction "2_2") (pintype "passive"))
      (node (ref "R325") (pin "1") (pinfunction "1_1") (pintype "passive"))
    )
    (net (code "18") (name "Net-(DA301-+)") (class "Default")
      (node (ref "DA301") (pin "2") (pinfunction "+_2") (pintype "passive"))
      (node (ref "R301") (pin "2") (pinfunction "2_2") (pintype "passive"))
    )
    (net (code "19") (name "Net-(DA301-CC1)") (class "Default")
      (node (ref "C306") (pin "1") (pinfunction "1_1") (pintype "passive"))
      (node (ref "DA301") (pin "6") (pinfunction "CC1_6") (pintype "passive"))
    )
    (net (code "20") (name "Net-(DA301-CC2)") (class "Default")
      (node (ref "C306") (pin "2") (pinfunction "2_2") (pintype "passive"))
      (node (ref "DA301") (pin "7") (pinfunction "CC2_7") (pintype "passive"))
    )
    (net (code "21") (name "Net-(DA301-Out)") (class "Default")
      (node (ref "C302") (pin "1") (pinfunction "1_1") (pintype "passive"))
      (node (ref "DA301") (pin "5") (pinfunction "Out_5") (pintype "passive"))
      (node (ref "KT301") (pin "1") (pinfunction "1_1") (pintype "passive"))
      (node (ref "R304") (pin "2") (pinfunction "2_2") (pintype "passive"))
    )
    (net (code "22") (name "Net-(R314-Pad1)") (class "Default")
      (node (ref "R314") (pin "1") (pinfunction "1_1") (pintype "passive"))
      (node (ref "VT305") (pin "2") (pinfunction "C_2") (pintype "passive"))
      (node (ref "VT305") (pin "4") (pinfunction "C_4") (pintype "passive"))
    )
    (net (code "23") (name "Net-(R320-Pad1)") (class "Default")
      (node (ref "R320") (pin "1") (pinfunction "1_1") (pintype "passive"))
      (node (ref "VT306") (pin "2") (pinfunction "C_2") (pintype "passive"))
      (node (ref "VT306") (pin "4") (pinfunction "C_4") (pintype "passive"))
    )
    (net (code "24") (name "Net-(R329-Pad1)") (class "Default")
      (node (ref "R329") (pin "1") (pinfunction "1_1") (pintype "passive"))
      (node (ref "VT310") (pin "1") (pinfunction "D_1") (pintype "passive"))
      (node (ref "VT310") (pin "2") (pinfunction "D_2") (pintype "passive"))
      (node (ref "VT310") (pin "5") (pinfunction "D_5") (pintype "passive"))
      (node (ref "VT310") (pin "6") (pinfunction "D_6") (pintype "passive"))
    )
    (net (code "25") (name "Net-(VD303-C)") (class "Default")
      (node (ref "R304") (pin "1") (pinfunction "1_1") (pintype "passive"))
      (node (ref "VD303") (pin "1") (pinfunction "C_1") (pintype "passive"))
      (node (ref "VD304") (pin "2") (pinfunction "A_2") (pintype "passive"))
    )
    (net (code "26") (name "Net-(VD304-C)") (class "Default")
      (node (ref "C310") (pin "1") (pinfunction "1_1") (pintype "passive"))
      (node (ref "R316") (pin "1") (pinfunction "1_1") (pintype "passive"))
      (node (ref "VD304") (pin "1") (pinfunction "C_1") (pintype "passive"))
      (node (ref "VT304") (pin "2") (pinfunction "C_2") (pintype "passive"))
      (node (ref "VT304") (pin "4") (pinfunction "C_4") (pintype "passive"))
    )
    (net (code "27") (name "Net-(VD305-A)") (class "Default")
      (node (ref "R313") (pin "2") (pinfunction "2_2") (pintype "passive"))
      (node (ref "VD305") (pin "2") (pinfunction "A_2") (pintype "passive"))
      (node (ref "VT305") (pin "3") (pinfunction "E_3") (pintype "passive"))
    )
    (net (code "28") (name "Net-(VD306-C)") (class "Default")
      (node (ref "R317") (pin "2") (pinfunction "2_2") (pintype "passive"))
      (node (ref "VD306") (pin "1") (pinfunction "C_1") (pintype "passive"))
      (node (ref "VT306") (pin "3") (pinfunction "E_3") (pintype "passive"))
    )
    (net (code "29") (name "Net-(VD307-A)") (class "Default")
      (node (ref "C313") (pin "1") (pinfunction "1_1") (pintype "passive"))
      (node (ref "C315") (pin "1") (pinfunction "1_1") (pintype "passive"))
      (node (ref "C316") (pin "1") (pinfunction "1_1") (pintype "passive"))
      (node (ref "VD307") (pin "2") (pinfunction "A_2") (pintype "passive"))
      (node (ref "VD308") (pin "1") (pinfunction "K_1") (pintype "passive"))
      (node (ref "VD309") (pin "1") (pinfunction "K_1") (pintype "passive"))
      (node (ref "VT309") (pin "1") (pinfunction "D_1") (pintype "passive"))
      (node (ref "VT309") (pin "2") (pinfunction "D_2") (pintype "passive"))
      (node (ref "VT309") (pin "5") (pinfunction "D_5") (pintype "passive"))
      (node (ref "VT309") (pin "6") (pinfunction "D_6") (pintype "passive"))
      (node (ref "VT311") (pin "2") (pinfunction "C_2") (pintype "passive"))
      (node (ref "VT311") (pin "4") (pinfunction "C_4") (pintype "passive"))
      (node (ref "VT312") (pin "2") (pinfunction "D_2") (pintype "passive"))
      (node (ref "VT315") (pin "2") (pinfunction "C_2") (pintype "passive"))
    )
    (net (code "30") (name "Net-(VD311-A)") (class "Default")
      (node (ref "C314") (pin "2") (pinfunction "2_2") (pintype "passive"))
      (node (ref "C317") (pin "2") (pinfunction "2_2") (pintype "passive"))
      (node (ref "C318") (pin "1") (pinfunction "1_1") (pintype "passive"))
      (node (ref "VD311") (pin "2") (pinfunction "A_2") (pintype "passive"))
      (node (ref "VD312") (pin "3") (pinfunction "A_3") (pintype "passive"))
      (node (ref "VD313") (pin "1") (pinfunction "K_1") (pintype "passive"))
      (node (ref "VT310") (pin "4") (pinfunction "S_4") (pintype "passive"))
      (node (ref "VT313") (pin "3") (pinfunction "S_3") (pintype "passive"))
      (node (ref "VT314") (pin "2") (pinfunction "C_2") (pintype "passive"))
      (node (ref "VT314") (pin "4") (pinfunction "C_4") (pintype "passive"))
      (node (ref "VT316") (pin "2") (pinfunction "C_2") (pintype "passive"))
    )
    (net (code "31") (name "Net-(VT301-B)") (class "Default")
      (node (ref "C309") (pin "2") (pinfunction "2_2") (pintype "passive"))
      (node (ref "R307") (pin "1") (pinfunction "1_1") (pintype "passive"))
      (node (ref "VT301") (pin "1") (pinfunction "B_1") (pintype "passive"))
      (node (ref "VT301") (pin "2") (pinfunction "C_2") (pintype "passive"))
      (node (ref "VT301") (pin "4") (pinfunction "C_4") (pintype "passive"))
      (node (ref "VT302") (pin "1") (pinfunction "B_1") (pintype "passive"))
    )
    (net (code "32") (name "Net-(VT301-E)") (class "Default")
      (node (ref "R305") (pin "2") (pinfunction "2_2") (pintype "passive"))
      (node (ref "VT301") (pin "3") (pinfunction "E_3") (pintype "passive"))
    )
    (net (code "33") (name "Net-(VT302-E)") (class "Default")
      (node (ref "R306") (pin "2") (pinfunction "2_2") (pintype "passive"))
      (node (ref "VT302") (pin "3") (pinfunction "E_3") (pintype "passive"))
    )
    (net (code "34") (name "Net-(VT303-B)") (class "Default")
      (node (ref "C310") (pin "2") (pinfunction "2_2") (pintype "passive"))
      (node (ref "R308") (pin "1") (pinfunction "1_1") (pintype "passive"))
      (node (ref "VT303") (pin "1") (pinfunction "B_1") (pintype "passive"))
      (node (ref "VT303") (pin "2") (pinfunction "C_2") (pintype "passive"))
      (node (ref "VT303") (pin "4") (pinfunction "C_4") (pintype "passive"))
      (node (ref "VT304") (pin "1") (pinfunction "B_1") (pintype "passive"))
    )
    (net (code "35") (name "Net-(VT303-E)") (class "Default")
      (node (ref "R309") (pin "2") (pinfunction "2_2") (pintype "passive"))
      (node (ref "VT303") (pin "3") (pinfunction "E_3") (pintype "passive"))
    )
    (net (code "36") (name "Net-(VT304-E)") (class "Default")
      (node (ref "R310") (pin "2") (pinfunction "2_2") (pintype "passive"))
      (node (ref "VT304") (pin "3") (pinfunction "E_3") (pintype "passive"))
    )
    (net (code "37") (name "Net-(VT305-B)") (class "Default")
      (node (ref "R311") (pin "2") (pinfunction "2_2") (pintype "passive"))
      (node (ref "R312") (pin "2") (pinfunction "2_2") (pintype "passive"))
      (node (ref "VT305") (pin "1") (pinfunction "B_1") (pintype "passive"))
    )
    (net (code "38") (name "Net-(VT306-B)") (class "Default")
      (node (ref "R318") (pin "2") (pinfunction "2_2") (pintype "passive"))
      (node (ref "R319") (pin "2") (pinfunction "2_2") (pintype "passive"))
      (node (ref "VT306") (pin "1") (pinfunction "B_1") (pintype "passive"))
    )
    (net (code "39") (name "Net-(VT307-B)") (class "Default")
      (node (ref "R323") (pin "1") (pinfunction "1_1") (pintype "passive"))
      (node (ref "VT307") (pin "1") (pinfunction "B_1") (pintype "passive"))
    )
    (net (code "40") (name "Net-(VT308-B)") (class "Default")
      (node (ref "R327") (pin "1") (pinfunction "1_1") (pintype "passive"))
      (node (ref "VT308") (pin "1") (pinfunction "B_1") (pintype "passive"))
    )
    (net (code "41") (name "Net-(VT309-G)") (class "Default")
      (node (ref "R315") (pin "2") (pinfunction "2_2") (pintype "passive"))
      (node (ref "VT307") (pin "2") (pinfunction "C_2") (pintype "passive"))
      (node (ref "VT307") (pin "4") (pinfunction "C_4") (pintype "passive"))
      (node (ref "VT309") (pin "3") (pinfunction "G_3") (pintype "passive"))
    )
    (net (code "42") (name "Net-(VT309-S)") (class "Default")
      (node (ref "R321") (pin "1") (pinfunction "1_1") (pintype "passive"))
      (node (ref "VT309") (pin "4") (pinfunction "S_4") (pintype "passive"))
    )
    (net (code "43") (name "Net-(VT310-G)") (class "Default")
      (node (ref "R316") (pin "2") (pinfunction "2_2") (pintype "passive"))
      (node (ref "VT308") (pin "2") (pinfunction "C_2") (pintype "passive"))
      (node (ref "VT308") (pin "4") (pinfunction "C_4") (pintype "passive"))
      (node (ref "VT310") (pin "3") (pinfunction "G_3") (pintype "passive"))
    )
    (net (code "44") (name "Net-(VT311-B)") (class "Default")
      (node (ref "R314") (pin "2") (pinfunction "2_2") (pintype "passive"))
      (node (ref "R330") (pin "1") (pinfunction "1_1") (pintype "passive"))
      (node (ref "VT311") (pin "1") (pinfunction "B_1") (pintype "passive"))
    )
    (net (code "45") (name "Net-(VT311-E)") (class "Default")
      (node (ref "VT311") (pin "3") (pinfunction "E_3") (pintype "passive"))
      (node (ref "VT315") (pin "1") (pinfunction "B_1") (pintype "passive"))
    )
    (net (code "46") (name "Net-(VT312-G)") (class "Default")
      (node (ref "C313") (pin "2") (pinfunction "2_2") (pintype "passive"))
      (node (ref "R321") (pin "2") (pinfunction "2_2") (pintype "passive"))
      (node (ref "R322") (pin "2") (pinfunction "2_2") (pintype "passive"))
      (node (ref "VT312") (pin "1") (pinfunction "G_1") (pintype "passive"))
    )
    (net (code "47") (name "Net-(VT312-S)") (class "Default")
      (node (ref "R322") (pin "1") (pinfunction "1_1") (pintype "passive"))
      (node (ref "R323") (pin "2") (pinfunction "2_2") (pintype "passive"))
      (node (ref "R324") (pin "2") (pinfunction "2_2") (pintype "passive"))
      (node (ref "VT312") (pin "3") (pinfunction "S_3") (pintype "passive"))
    )
    (net (code "48") (name "Net-(VT313-D)") (class "Default")
      (node (ref "R326") (pin "1") (pinfunction "1_1") (pintype "passive"))
      (node (ref "R327") (pin "2") (pinfunction "2_2") (pintype "passive"))
      (node (ref "R328") (pin "2") (pinfunction "2_2") (pintype "passive"))
      (node (ref "VT313") (pin "2") (pinfunction "D_2") (pintype "passive"))
    )
    (net (code "49") (name "Net-(VT313-G)") (class "Default")
      (node (ref "C314") (pin "1") (pinfunction "1_1") (pintype "passive"))
      (node (ref "R328") (pin "1") (pinfunction "1_1") (pintype "passive"))
      (node (ref "R329") (pin "2") (pinfunction "2_2") (pintype "passive"))
      (node (ref "VT313") (pin "1") (pinfunction "G_1") (pintype "passive"))
    )
    (net (code "50") (name "Net-(VT314-B)") (class "Default")
      (node (ref "R320") (pin "2") (pinfunction "2_2") (pintype "passive"))
      (node (ref "R331") (pin "1") (pinfunction "1_1") (pintype "passive"))
      (node (ref "VT314") (pin "1") (pinfunction "B_1") (pintype "passive"))
    )
    (net (code "51") (name "Net-(VT314-E)") (class "Default")
      (node (ref "VT314") (pin "3") (pinfunction "E_3") (pintype "passive"))
      (node (ref "VT316") (pin "1") (pinfunction "B_1") (pintype "passive"))
    )
    (net (code "52") (name "PR") (class "Default")
      (node (ref "C309") (pin "1") (pinfunction "1_1") (pintype "passive"))
      (node (ref "R315") (pin "1") (pinfunction "1_1") (pintype "passive"))
      (node (ref "VD303") (pin "2") (pinfunction "A_2") (pintype "passive"))
      (node (ref "VT302") (pin "2") (pinfunction "C_2") (pintype "passive"))
      (node (ref "VT302") (pin "4") (pinfunction "C_4") (pintype "passive"))
    )
  )
)
